# OpAmp_Channnels.net
KiCad netlist of a schematic drawn in Altium Designer
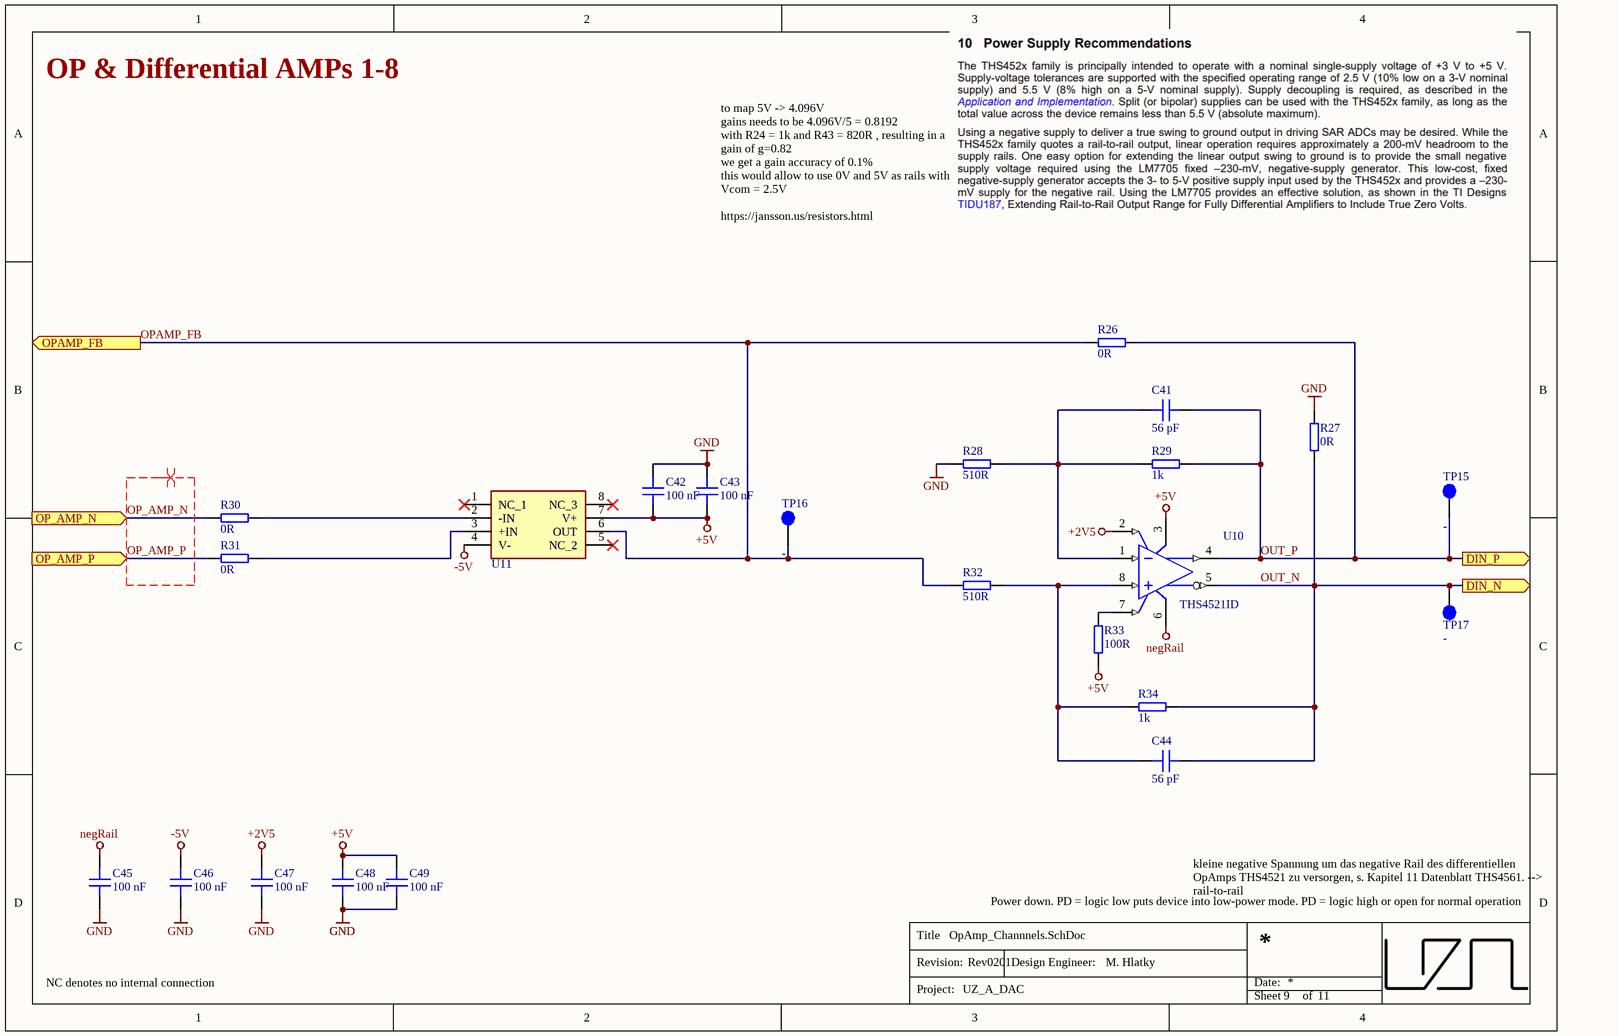
[diagram p0: OpAmp_Channnels.SchDoc]

(export (version "E")
  (design (tool "Eeschema 10.0.6"))
  (components
    (comp (ref "C41")
      (value "56 pF")
      (footprint "C_0603")
      (description "Capacitor 0603, 50 VDC, 56 pF, C0G")
      (fields
        (field (name "MANUFACTURER PART NUMBER") "VJ0603A560JXACW1BC")
        (field (name "MANUFACTURER") "Vishay")
        (field (name "CREATED FROM") "MGremer")
      )
      (libsource (lib "user") (part "Capacitor"))
    )
    (comp (ref "C42")
      (value "100 nF")
      (footprint "C_0603")
      (description "Capacitor 0603, 6.3 VDC, 100 nF, X5R")
      (fields
        (field (name "MANUFACTURER PART NUMBER") "C0603C104K9PACTU")
        (field (name "MANUFACTURER") "KEMET")
        (field (name "CREATED FROM") "MGremer")
      )
      (libsource (lib "user") (part "Capacitor"))
    )
    (comp (ref "C43")
      (value "100 nF")
      (footprint "C_0603")
      (description "Capacitor 0603, 6.3 VDC, 100 nF, X5R")
      (fields
        (field (name "MANUFACTURER PART NUMBER") "C0603C104K9PACTU")
        (field (name "MANUFACTURER") "KEMET")
        (field (name "CREATED FROM") "MGremer")
      )
      (libsource (lib "user") (part "Capacitor"))
    )
    (comp (ref "C44")
      (value "56 pF")
      (footprint "C_0603")
      (description "Capacitor 0603, 50 VDC, 56 pF, C0G")
      (fields
        (field (name "MANUFACTURER PART NUMBER") "VJ0603A560JXACW1BC")
        (field (name "MANUFACTURER") "Vishay")
        (field (name "CREATED FROM") "MGremer")
      )
      (libsource (lib "user") (part "Capacitor"))
    )
    (comp (ref "C45")
      (value "100 nF")
      (footprint "C_0603")
      (description "Capacitor 0603, 6.3 VDC, 100 nF, X5R")
      (fields
        (field (name "MANUFACTURER PART NUMBER") "C0603C104K9PACTU")
        (field (name "MANUFACTURER") "KEMET")
        (field (name "CREATED FROM") "MGremer")
      )
      (libsource (lib "user") (part "Capacitor"))
    )
    (comp (ref "C46")
      (value "100 nF")
      (footprint "C_0603")
      (description "Capacitor 0603, 6.3 VDC, 100 nF, X5R")
      (fields
        (field (name "MANUFACTURER PART NUMBER") "C0603C104K9PACTU")
        (field (name "MANUFACTURER") "KEMET")
        (field (name "CREATED FROM") "MGremer")
      )
      (libsource (lib "user") (part "Capacitor"))
    )
    (comp (ref "C47")
      (value "100 nF")
      (footprint "C_0603")
      (description "Capacitor 0603, 6.3 VDC, 100 nF, X5R")
      (fields
        (field (name "MANUFACTURER PART NUMBER") "C0603C104K9PACTU")
        (field (name "MANUFACTURER") "KEMET")
        (field (name "CREATED FROM") "MGremer")
      )
      (libsource (lib "user") (part "Capacitor"))
    )
    (comp (ref "C48")
      (value "100 nF")
      (footprint "C_0603")
      (description "Capacitor 0603, 6.3 VDC, 100 nF, X5R")
      (fields
        (field (name "MANUFACTURER PART NUMBER") "C0603C104K9PACTU")
        (field (name "MANUFACTURER") "KEMET")
        (field (name "CREATED FROM") "MGremer")
      )
      (libsource (lib "user") (part "Capacitor"))
    )
    (comp (ref "C49")
      (value "100 nF")
      (footprint "C_0603")
      (description "Capacitor 0603, 6.3 VDC, 100 nF, X5R")
      (fields
        (field (name "MANUFACTURER PART NUMBER") "C0603C104K9PACTU")
        (field (name "MANUFACTURER") "KEMET")
        (field (name "CREATED FROM") "MGremer")
      )
      (libsource (lib "user") (part "Capacitor"))
    )
    (comp (ref "R26")
      (value "0R")
      (footprint "RES 0603_1608")
      (description "SMD resistor E24 series")
      (fields
        (field (name "MANUFACTURER PART NUMBER") "RC0603JR-070RL")
        (field (name "MANUFACTURER") "YAGEO")
        (field (name "CREATED FROM") "MGremer")
      )
      (libsource (lib "user") (part "Resistor"))
    )
    (comp (ref "R27")
      (value "0R")
      (footprint "RES 0603_1608")
      (description "SMD resistor E24 series")
      (fields
        (field (name "MANUFACTURER PART NUMBER") "RC0603JR-070RL")
        (field (name "MANUFACTURER") "YAGEO")
        (field (name "CREATED FROM") "MGremer")
      )
      (libsource (lib "user") (part "Resistor"))
    )
    (comp (ref "R28")
      (value "510R")
      (footprint "RES 0603_1608")
      (description "SMD resistor E24 series")
      (fields
        (field (name "MANUFACTURER PART NUMBER") "RK73B1JTTD511J")
        (field (name "MANUFACTURER") "KOA Speer")
        (field (name "CREATED FROM") "MGremer")
      )
      (libsource (lib "user") (part "Resistor"))
    )
    (comp (ref "R29")
      (value "1k")
      (footprint "RES 0603_1608")
      (description "SMD resistor E24 series")
      (fields
        (field (name "MANUFACTURER PART NUMBER") "RK73B1JTTDD102J")
        (field (name "MANUFACTURER") "KOA Speer")
        (field (name "CREATED FROM") "MGremer")
      )
      (libsource (lib "user") (part "Resistor"))
    )
    (comp (ref "R30")
      (value "0R")
      (footprint "RES 0603_1608")
      (description "SMD resistor E24 series")
      (fields
        (field (name "MANUFACTURER PART NUMBER") "RC0603JR-070RL")
        (field (name "MANUFACTURER") "YAGEO")
        (field (name "CREATED FROM") "MGremer")
      )
      (libsource (lib "user") (part "Resistor"))
    )
    (comp (ref "R31")
      (value "0R")
      (footprint "RES 0603_1608")
      (description "SMD resistor E24 series")
      (fields
        (field (name "MANUFACTURER PART NUMBER") "RC0603JR-070RL")
        (field (name "MANUFACTURER") "YAGEO")
        (field (name "CREATED FROM") "MGremer")
      )
      (libsource (lib "user") (part "Resistor"))
    )
    (comp (ref "R32")
      (value "510R")
      (footprint "RES 0603_1608")
      (description "SMD resistor E24 series")
      (fields
        (field (name "MANUFACTURER PART NUMBER") "RK73B1JTTD511J")
        (field (name "MANUFACTURER") "KOA Speer")
        (field (name "CREATED FROM") "MGremer")
      )
      (libsource (lib "user") (part "Resistor"))
    )
    (comp (ref "R33")
      (value "100R")
      (footprint "RES 0603_1608")
      (description "SMD resistor 1%")
      (fields
        (field (name "MANUFACTURER PART NUMBER") "AC0603FR-13100RL")
        (field (name "MANUFACTURER") "Yageo")
        (field (name "CREATED FROM") "MGremer")
      )
      (libsource (lib "user") (part "Resistor"))
    )
    (comp (ref "R34")
      (value "1k")
      (footprint "RES 0603_1608")
      (description "SMD resistor E24 series")
      (fields
        (field (name "MANUFACTURER PART NUMBER") "RK73B1JTTDD102J")
        (field (name "MANUFACTURER") "KOA Speer")
        (field (name "CREATED FROM") "MGremer")
      )
      (libsource (lib "user") (part "Resistor"))
    )
    (comp (ref "TP15")
      (value "-")
      (footprint "TP_1mm")
      (description "Test Point 1 mm")
      (fields (field (name "CREATED") "2018_06_25_AGeiger") (field (name "CREATED FROM") "MGremer"))
      (libsource (lib "user") (part "TP_1mm"))
    )
    (comp (ref "TP16")
      (value "-")
      (footprint "TP_1mm")
      (description "Test Point 1 mm")
      (fields (field (name "CREATED") "2018_06_25_AGeiger") (field (name "CREATED FROM") "MGremer"))
      (libsource (lib "user") (part "TP_1mm"))
    )
    (comp (ref "TP17")
      (value "-")
      (footprint "TP_1mm")
      (description "Test Point 1 mm")
      (fields (field (name "CREATED") "2018_06_25_AGeiger") (field (name "CREATED FROM") "MGremer"))
      (libsource (lib "user") (part "TP_1mm"))
    )
    (comp (ref "U10")
      (value "THS4521ID")
      (footprint "D0008A_M")
      (description "Very Low Power, Negative Rail Input, Rail-To-Rail Output, Fully Differential Amplifier")
      (fields (field (name "MANUFACTURER") "TI") (field (name "CREATED FROM") "MHlatky"))
      (libsource (lib "user") (part "THS4521ID"))
    )
    (comp (ref "U11")
      (value "OPA727AIDGKT")
      (footprint "SOP65P490X110-8N")
      (description "e-trim™ 20MHz, High Precision CMOS Operational Amplifier")
      (fields (field (name "MANUFACTURER") "TI") (field (name "CREATED FROM") "MHlatky"))
      (libsource (lib "user") (part "OPA727AIDGKT"))
    )
  )
  (nets
    (net (code "1") (name "+2V5") (class "Default")
      (node (ref "C47") (pin "2") (pinfunction "2_2") (pintype "passive"))
      (node (ref "U10") (pin "2") (pinfunction "VOCM_2") (pintype "input"))
    )
    (net (code "2") (name "+5V") (class "Default")
      (node (ref "C42") (pin "1") (pinfunction "1_1") (pintype "passive"))
      (node (ref "C43") (pin "1") (pinfunction "1_1") (pintype "passive"))
      (node (ref "C48") (pin "2") (pinfunction "2_2") (pintype "passive"))
      (node (ref "C49") (pin "2") (pinfunction "2_2") (pintype "passive"))
      (node (ref "R33") (pin "2") (pinfunction "2_2") (pintype "passive"))
      (node (ref "U10") (pin "3") (pinfunction "VS+_3") (pintype "power_in"))
      (node (ref "U11") (pin "7") (pinfunction "V+_7") (pintype "passive"))
    )
    (net (code "3") (name "-5V") (class "Default")
      (node (ref "C46") (pin "2") (pinfunction "2_2") (pintype "passive"))
      (node (ref "U11") (pin "4") (pinfunction "V-_4") (pintype "passive"))
    )
    (net (code "4") (name "/OPAMP_FB") (class "Default")
      (node (ref "R26") (pin "1") (pinfunction "1_1") (pintype "passive"))
      (node (ref "R32") (pin "1") (pinfunction "1_1") (pintype "passive"))
      (node (ref "TP16") (pin "1") (pintype "passive"))
      (node (ref "U11") (pin "6") (pinfunction "OUT_6") (pintype "passive"))
    )
    (net (code "5") (name "/OP_AMP_N") (class "Default")
      (node (ref "R30") (pin "1") (pinfunction "1_1") (pintype "passive"))
    )
    (net (code "6") (name "/OP_AMP_P") (class "Default")
      (node (ref "R31") (pin "1") (pinfunction "1_1") (pintype "passive"))
    )
    (net (code "7") (name "/OUT_N") (class "Default")
      (node (ref "C44") (pin "2") (pinfunction "2_2") (pintype "passive"))
      (node (ref "R27") (pin "1") (pinfunction "1_1") (pintype "passive"))
      (node (ref "R34") (pin "2") (pinfunction "2_2") (pintype "passive"))
      (node (ref "TP17") (pin "1") (pintype "passive"))
      (node (ref "U10") (pin "5") (pinfunction "VOUT-_5") (pintype "output"))
    )
    (net (code "8") (name "/OUT_P") (class "Default")
      (node (ref "C41") (pin "2") (pinfunction "2_2") (pintype "passive"))
      (node (ref "R26") (pin "2") (pinfunction "2_2") (pintype "passive"))
      (node (ref "R29") (pin "2") (pinfunction "2_2") (pintype "passive"))
      (node (ref "TP15") (pin "1") (pintype "passive"))
      (node (ref "U10") (pin "4") (pinfunction "VOUT+_4") (pintype "output"))
    )
    (net (code "9") (name "GND") (class "Default")
      (node (ref "C42") (pin "2") (pinfunction "2_2") (pintype "passive"))
      (node (ref "C43") (pin "2") (pinfunction "2_2") (pintype "passive"))
      (node (ref "C45") (pin "1") (pinfunction "1_1") (pintype "passive"))
      (node (ref "C46") (pin "1") (pinfunction "1_1") (pintype "passive"))
      (node (ref "C47") (pin "1") (pinfunction "1_1") (pintype "passive"))
      (node (ref "C48") (pin "1") (pinfunction "1_1") (pintype "passive"))
      (node (ref "C49") (pin "1") (pinfunction "1_1") (pintype "passive"))
      (node (ref "R27") (pin "2") (pinfunction "2_2") (pintype "passive"))
      (node (ref "R28") (pin "1") (pinfunction "1_1") (pintype "passive"))
    )
    (net (code "10") (name "Net-(U10-VIN+)") (class "Default")
      (node (ref "C44") (pin "1") (pinfunction "1_1") (pintype "passive"))
      (node (ref "R32") (pin "2") (pinfunction "2_2") (pintype "passive"))
      (node (ref "R34") (pin "1") (pinfunction "1_1") (pintype "passive"))
      (node (ref "U10") (pin "8") (pinfunction "VIN+_8") (pintype "input"))
    )
    (net (code "11") (name "Net-(U10-VIN-)") (class "Default")
      (node (ref "C41") (pin "1") (pinfunction "1_1") (pintype "passive"))
      (node (ref "R28") (pin "2") (pinfunction "2_2") (pintype "passive"))
      (node (ref "R29") (pin "1") (pinfunction "1_1") (pintype "passive"))
      (node (ref "U10") (pin "1") (pinfunction "VIN-_1") (pintype "input"))
    )
    (net (code "12") (name "Net-(U10-~{PD})") (class "Default")
      (node (ref "R33") (pin "1") (pinfunction "1_1") (pintype "passive"))
      (node (ref "U10") (pin "7") (pinfunction "~{PD}_7") (pintype "input"))
    )
    (net (code "13") (name "Net-(U11-+IN)") (class "Default")
      (node (ref "R31") (pin "2") (pinfunction "2_2") (pintype "passive"))
      (node (ref "U11") (pin "3") (pinfunction "+IN_3") (pintype "passive"))
    )
    (net (code "14") (name "Net-(U11--IN)") (class "Default")
      (node (ref "R30") (pin "2") (pinfunction "2_2") (pintype "passive"))
      (node (ref "U11") (pin "2") (pinfunction "-IN_2") (pintype "passive"))
    )
    (net (code "15") (name "negRail") (class "Default")
      (node (ref "C45") (pin "2") (pinfunction "2_2") (pintype "passive"))
      (node (ref "U10") (pin "6") (pinfunction "VS-_6") (pintype "power_in"))
    )
    (net (code "16") (name "unconnected-(U11-NC_1-Pad1)") (class "Default")
      (node (ref "U11") (pin "1") (pinfunction "NC_1_1") (pintype "passive+no_connect"))
    )
    (net (code "17") (name "unconnected-(U11-NC_2-Pad5)") (class "Default")
      (node (ref "U11") (pin "5") (pinfunction "NC_2_5") (pintype "passive+no_connect"))
    )
    (net (code "18") (name "unconnected-(U11-NC_3-Pad8)") (class "Default")
      (node (ref "U11") (pin "8") (pinfunction "NC_3_8") (pintype "passive+no_connect"))
    )
  )
)
